# RPi_SyncInputAdapter_Schematic.net
KiCad netlist of a schematic drawn in Altium Designer
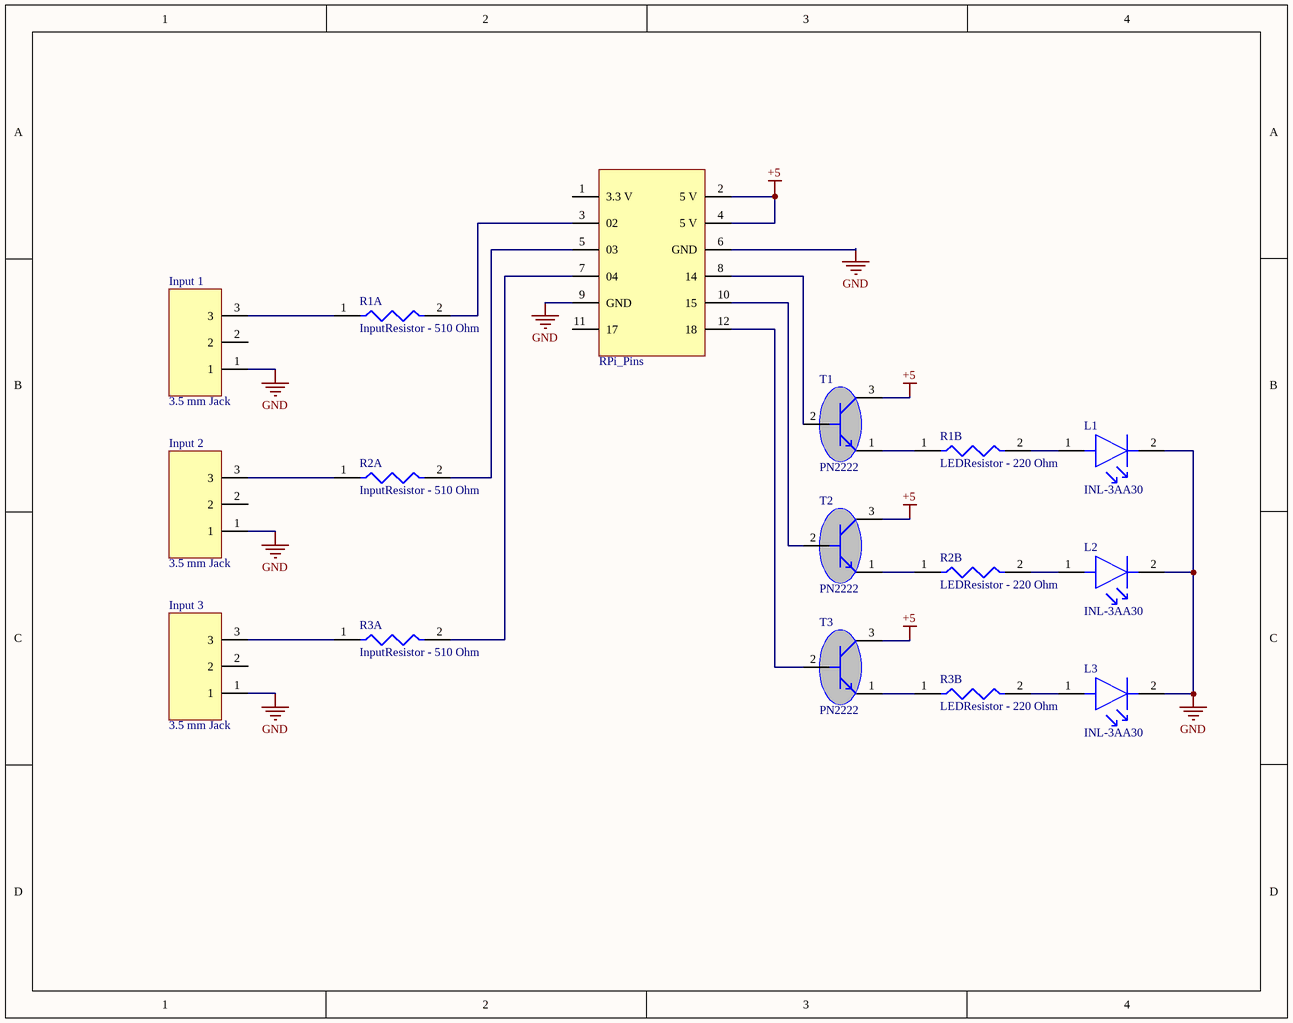
[diagram p0: RPi_SyncInputAdapter_Schematic.SchDoc]

(export (version "E")
  (design (tool "Eeschema 10.0.6"))
  (components
    (comp (ref "*")
      (value "RPi_Pins")
      (footprint "RPi_Interface")
      (libsource (lib "RPi_SyncInputAdapter_SchLib") (part "RPi_Pins"))
    )
    (comp (ref "Input 1")
      (value "3.5 mm Jack")
      (footprint "3PolesAudioJack_SMD")
      (description "CONN JACK STEREO 3.5MM SMD R/A")
      (fields (field (name "MANUFACTURER") "CUI") (field (name "MANUFACTURER PART NUMBER") "SJ-3523-SMT-TR"))
      (libsource (lib "RPi_SyncInputAdapter_SchLib") (part "SJ-3523-SMT-TR"))
    )
    (comp (ref "Input 2")
      (value "3.5 mm Jack")
      (footprint "3PolesAudioJack_SMD")
      (description "CONN JACK STEREO 3.5MM SMD R/A")
      (fields (field (name "MANUFACTURER") "CUI") (field (name "MANUFACTURER PART NUMBER") "SJ-3523-SMT-TR"))
      (libsource (lib "RPi_SyncInputAdapter_SchLib") (part "SJ-3523-SMT-TR"))
    )
    (comp (ref "Input 3")
      (value "3.5 mm Jack")
      (footprint "3PolesAudioJack_SMD")
      (description "CONN JACK STEREO 3.5MM SMD R/A")
      (fields (field (name "MANUFACTURER") "CUI") (field (name "MANUFACTURER PART NUMBER") "SJ-3523-SMT-TR"))
      (libsource (lib "RPi_SyncInputAdapter_SchLib") (part "SJ-3523-SMT-TR"))
    )
    (comp (ref "L1")
      (value "INL-3AA30")
      (footprint "LED")
      (description "LED AMBER CLEAR 3MM T/H")
      (fields (field (name "MANUFACTURER") "Inolux"))
      (libsource (lib "RPi_SyncInputAdapter_SchLib") (part "INL-3AA30"))
    )
    (comp (ref "L2")
      (value "INL-3AA30")
      (footprint "LED")
      (description "LED AMBER CLEAR 3MM T/H")
      (fields (field (name "MANUFACTURER") "Inolux"))
      (libsource (lib "RPi_SyncInputAdapter_SchLib") (part "INL-3AA30"))
    )
    (comp (ref "L3")
      (value "INL-3AA30")
      (footprint "LED")
      (description "LED AMBER CLEAR 3MM T/H")
      (fields (field (name "MANUFACTURER") "Inolux"))
      (libsource (lib "RPi_SyncInputAdapter_SchLib") (part "INL-3AA30"))
    )
    (comp (ref "R1A")
      (value "InputResistor - 510 Ohm")
      (footprint "TypicalResistor")
      (libsource (lib "RPi_SyncInputAdapter_SchLib") (part "InputResistor"))
    )
    (comp (ref "R1B")
      (value "LEDResistor - 220 Ohm")
      (footprint "TypicalResistor")
      (libsource (lib "RPi_SyncInputAdapter_SchLib") (part "LEDResistor"))
    )
    (comp (ref "R2A")
      (value "InputResistor - 510 Ohm")
      (footprint "TypicalResistor")
      (libsource (lib "RPi_SyncInputAdapter_SchLib") (part "InputResistor"))
    )
    (comp (ref "R2B")
      (value "LEDResistor - 220 Ohm")
      (footprint "TypicalResistor")
      (libsource (lib "RPi_SyncInputAdapter_SchLib") (part "LEDResistor"))
    )
    (comp (ref "R3A")
      (value "InputResistor - 510 Ohm")
      (footprint "TypicalResistor")
      (libsource (lib "RPi_SyncInputAdapter_SchLib") (part "InputResistor"))
    )
    (comp (ref "R3B")
      (value "LEDResistor - 220 Ohm")
      (footprint "TypicalResistor")
      (libsource (lib "RPi_SyncInputAdapter_SchLib") (part "LEDResistor"))
    )
    (comp (ref "T1")
      (value "PN2222")
      (footprint "PN2222_Transistor")
      (description "TRANS NPN 30V 0.6A TO92")
      (fields (field (name "MANUFACTURER") "ON Semiconductor / Fairchild"))
      (libsource (lib "RPi_SyncInputAdapter_SchLib") (part "PN2222"))
    )
    (comp (ref "T2")
      (value "PN2222")
      (footprint "PN2222_Transistor")
      (description "TRANS NPN 30V 0.6A TO92")
      (fields (field (name "MANUFACTURER") "ON Semiconductor / Fairchild"))
      (libsource (lib "RPi_SyncInputAdapter_SchLib") (part "PN2222"))
    )
    (comp (ref "T3")
      (value "PN2222")
      (footprint "PN2222_Transistor")
      (description "TRANS NPN 30V 0.6A TO92")
      (fields (field (name "MANUFACTURER") "ON Semiconductor / Fairchild"))
      (libsource (lib "RPi_SyncInputAdapter_SchLib") (part "PN2222"))
    )
  )
  (nets
    (net (code "1") (name "+5") (class "Default")
      (node (ref "*") (pin "2") (pinfunction "5_V_2") (pintype "passive"))
      (node (ref "*") (pin "4") (pinfunction "5_V_4") (pintype "passive"))
      (node (ref "T1") (pin "3") (pinfunction "3_3") (pintype "passive"))
      (node (ref "T2") (pin "3") (pinfunction "3_3") (pintype "passive"))
      (node (ref "T3") (pin "3") (pinfunction "3_3") (pintype "passive"))
    )
    (net (code "2") (name "GND") (class "Default")
      (node (ref "*") (pin "6") (pinfunction "GND_6") (pintype "passive"))
      (node (ref "*") (pin "9") (pinfunction "GND_9") (pintype "passive"))
      (node (ref "Input 1") (pin "1") (pinfunction "1_1") (pintype "passive"))
      (node (ref "Input 2") (pin "1") (pinfunction "1_1") (pintype "passive"))
      (node (ref "Input 3") (pin "1") (pinfunction "1_1") (pintype "passive"))
      (node (ref "L1") (pin "2") (pinfunction "2_2") (pintype "passive"))
      (node (ref "L2") (pin "2") (pinfunction "2_2") (pintype "passive"))
      (node (ref "L3") (pin "2") (pinfunction "2_2") (pintype "passive"))
    )
    (net (code "3") (name "Net-(*-02)") (class "Default")
      (node (ref "*") (pin "3") (pinfunction "02_3") (pintype "passive"))
      (node (ref "R1A") (pin "2") (pinfunction "2_2") (pintype "passive"))
    )
    (net (code "4") (name "Net-(*-03)") (class "Default")
      (node (ref "*") (pin "5") (pinfunction "03_5") (pintype "passive"))
      (node (ref "R2A") (pin "2") (pinfunction "2_2") (pintype "passive"))
    )
    (net (code "5") (name "Net-(*-04)") (class "Default")
      (node (ref "*") (pin "7") (pinfunction "04_7") (pintype "passive"))
      (node (ref "R3A") (pin "2") (pinfunction "2_2") (pintype "passive"))
    )
    (net (code "6") (name "Net-(*-14)") (class "Default")
      (node (ref "*") (pin "8") (pinfunction "14_8") (pintype "passive"))
      (node (ref "T1") (pin "2") (pinfunction "2_2") (pintype "passive"))
    )
    (net (code "7") (name "Net-(*-15)") (class "Default")
      (node (ref "*") (pin "10") (pinfunction "15_10") (pintype "passive"))
      (node (ref "T2") (pin "2") (pinfunction "2_2") (pintype "passive"))
    )
    (net (code "8") (name "Net-(*-18)") (class "Default")
      (node (ref "*") (pin "12") (pinfunction "18_12") (pintype "passive"))
      (node (ref "T3") (pin "2") (pinfunction "2_2") (pintype "passive"))
    )
    (net (code "9") (name "Net-(Input 1-Pad3)") (class "Default")
      (node (ref "Input 1") (pin "3") (pinfunction "3_3") (pintype "passive"))
      (node (ref "R1A") (pin "1") (pinfunction "1_1") (pintype "passive"))
    )
    (net (code "10") (name "Net-(Input 2-Pad3)") (class "Default")
      (node (ref "Input 2") (pin "3") (pinfunction "3_3") (pintype "passive"))
      (node (ref "R2A") (pin "1") (pinfunction "1_1") (pintype "passive"))
    )
    (net (code "11") (name "Net-(Input 3-Pad3)") (class "Default")
      (node (ref "Input 3") (pin "3") (pinfunction "3_3") (pintype "passive"))
      (node (ref "R3A") (pin "1") (pinfunction "1_1") (pintype "passive"))
    )
    (net (code "12") (name "Net-(L1-Pad1)") (class "Default")
      (node (ref "L1") (pin "1") (pinfunction "1_1") (pintype "passive"))
      (node (ref "R1B") (pin "2") (pinfunction "2_2") (pintype "passive"))
    )
    (net (code "13") (name "Net-(L2-Pad1)") (class "Default")
      (node (ref "L2") (pin "1") (pinfunction "1_1") (pintype "passive"))
      (node (ref "R2B") (pin "2") (pinfunction "2_2") (pintype "passive"))
    )
    (net (code "14") (name "Net-(L3-Pad1)") (class "Default")
      (node (ref "L3") (pin "1") (pinfunction "1_1") (pintype "passive"))
      (node (ref "R3B") (pin "2") (pinfunction "2_2") (pintype "passive"))
    )
    (net (code "15") (name "Net-(R1B-Pad1)") (class "Default")
      (node (ref "R1B") (pin "1") (pinfunction "1_1") (pintype "passive"))
      (node (ref "T1") (pin "1") (pinfunction "1_1") (pintype "passive"))
    )
    (net (code "16") (name "Net-(R2B-Pad1)") (class "Default")
      (node (ref "R2B") (pin "1") (pinfunction "1_1") (pintype "passive"))
      (node (ref "T2") (pin "1") (pinfunction "1_1") (pintype "passive"))
    )
    (net (code "17") (name "Net-(R3B-Pad1)") (class "Default")
      (node (ref "R3B") (pin "1") (pinfunction "1_1") (pintype "passive"))
      (node (ref "T3") (pin "1") (pinfunction "1_1") (pintype "passive"))
    )
    (net (code "18") (name "unconnected-(*-3.3_V-Pad1)") (class "Default")
      (node (ref "*") (pin "1") (pinfunction "3.3_V_1") (pintype "passive"))
    )
    (net (code "19") (name "unconnected-(*-17-Pad11)") (class "Default")
      (node (ref "*") (pin "11") (pinfunction "17_11") (pintype "passive"))
    )
    (net (code "20") (name "unconnected-(Input 1-Pad2)") (class "Default")
      (node (ref "Input 1") (pin "2") (pinfunction "2_2") (pintype "passive"))
    )
    (net (code "21") (name "unconnected-(Input 2-Pad2)") (class "Default")
      (node (ref "Input 2") (pin "2") (pinfunction "2_2") (pintype "passive"))
    )
    (net (code "22") (name "unconnected-(Input 3-Pad2)") (class "Default")
      (node (ref "Input 3") (pin "2") (pinfunction "2_2") (pintype "passive"))
    )
  )
)
